# PWR_BUCK_6V_8A.net
KiCad netlist of a schematic drawn in Altium Designer
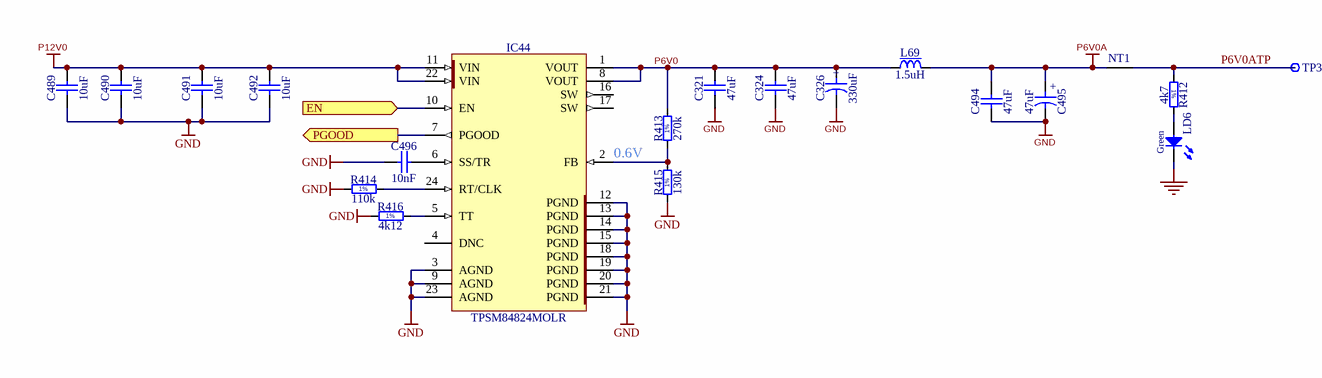
[diagram p0: PWR_BUCK_6V_8A.SchDoc]

(export (version "E")
  (design (tool "Eeschema 10.0.6"))
  (components
    (comp (ref "C321")
      (value "47uF")
      (footprint "CAPC3225X270N")
      (description "Non-polarised capacitor")
      (fields
        (field (name "MANUFACTURER PART NUMBER") "CC1210_47UF_10V_10%_X7R")
        (field (name "MANUFACTURER") "GENERIC")
        (field (name "AUTHOR") "CERN DEM BC")
      )
      (libsource (lib "Capacitors") (part "Capacitor - non polarized"))
    )
    (comp (ref "C324")
      (value "47uF")
      (footprint "CAPC3225X270N")
      (description "Non-polarised capacitor")
      (fields
        (field (name "MANUFACTURER PART NUMBER") "CC1210_47UF_10V_10%_X7R")
        (field (name "MANUFACTURER") "GENERIC")
        (field (name "AUTHOR") "CERN DEM BC")
      )
      (libsource (lib "Capacitors") (part "Capacitor - non polarized"))
    )
    (comp (ref "C326")
      (value "330uF")
      (footprint "CAPMP7343X310N")
      (description "Polarised capacitor")
      (fields
        (field (name "MANUFACTURER PART NUMBER") "T520D337M006ATE015")
        (field (name "MANUFACTURER") "KEMET")
        (field (name "AUTHOR") "CERN DEM JLC")
      )
      (libsource (lib "") (part "Capacitor - polarized_1"))
    )
    (comp (ref "C489")
      (value "10uF")
      (footprint "CAPC2012X95N")
      (description "Non-polarised capacitor")
      (fields
        (field (name "MANUFACTURER PART NUMBER") "CC0805_10UF_25V_10%_X5R")
        (field (name "MANUFACTURER") "GENERIC")
        (field (name "AUTHOR") "CERN DEM JLC")
      )
      (libsource (lib "Capacitors") (part "Capacitor - non polarized"))
    )
    (comp (ref "C490")
      (value "10uF")
      (footprint "CAPC2012X95N")
      (description "Non-polarised capacitor")
      (fields
        (field (name "MANUFACTURER PART NUMBER") "CC0805_10UF_25V_10%_X5R")
        (field (name "MANUFACTURER") "GENERIC")
        (field (name "AUTHOR") "CERN DEM JLC")
      )
      (libsource (lib "Capacitors") (part "Capacitor - non polarized"))
    )
    (comp (ref "C491")
      (value "10uF")
      (footprint "CAPC2012X95N")
      (description "Non-polarised capacitor")
      (fields
        (field (name "MANUFACTURER PART NUMBER") "CC0805_10UF_25V_10%_X5R")
        (field (name "MANUFACTURER") "GENERIC")
        (field (name "AUTHOR") "CERN DEM JLC")
      )
      (libsource (lib "Capacitors") (part "Capacitor - non polarized"))
    )
    (comp (ref "C492")
      (value "10uF")
      (footprint "CAPC2012X95N")
      (description "Non-polarised capacitor")
      (fields
        (field (name "MANUFACTURER PART NUMBER") "CC0805_10UF_25V_10%_X5R")
        (field (name "MANUFACTURER") "GENERIC")
        (field (name "AUTHOR") "CERN DEM JLC")
      )
      (libsource (lib "Capacitors") (part "Capacitor - non polarized"))
    )
    (comp (ref "C494")
      (value "47uF")
      (footprint "CAPC3225X270N")
      (description "Non-polarised capacitor")
      (fields
        (field (name "MANUFACTURER PART NUMBER") "CC1210_47UF_10V_10%_X7R")
        (field (name "MANUFACTURER") "GENERIC")
        (field (name "AUTHOR") "CERN DEM BC")
      )
      (libsource (lib "Capacitors") (part "Capacitor - non polarized"))
    )
    (comp (ref "C495")
      (value "47uF")
      (footprint "CAPMP6032X280N")
      (description "Polarised capacitor")
      (fields
        (field (name "MANUFACTURER PART NUMBER") "CTE6032-28_47UF_16V_10%_LESR0350")
        (field (name "MANUFACTURER") "GENERIC")
        (field (name "AUTHOR") "CERN DEM JLC")
      )
      (libsource (lib "Capacitors") (part "Capacitor - polarized"))
    )
    (comp (ref "C496")
      (value "10nF")
      (footprint "CAPC1005X55N")
      (description "Non-polarised capacitor")
      (fields
        (field (name "PART NUMBER") "CC0402_10NF_16V_10%_X7R")
        (field (name "VOLTAGE") "16V")
        (field (name "AUTHOR") "CERN DEM JLC")
      )
      (libsource (lib "Capacitors") (part "Capacitor - non polarized"))
    )
    (comp (ref "IC44")
      (value "TPSM84824MOLR")
      (footprint "TEXAS_QFM (MOL)")
      (description "4.5V to 17V Input, 0.6V to 10V Output, 8A Power Module")
      (fields (field (name "MANUFACTURER") "TEXAS INSTRUMENTS") (field (name "AUTHOR") "CERN DEM JLC"))
      (libsource (lib "ICs And Semiconductors") (part "TPSM84824"))
    )
    (comp (ref "L69")
      (value "1.5uH")
      (footprint "IND_TDK_SPM6530")
      (description "Inductor With Core")
      (fields
        (field (name "MANUFACTURER PART NUMBER") "SPM6530T-1R5M100")
        (field (name "MANUFACTURER") "TDK")
        (field (name "AUTHOR") "CERN DEM MR")
      )
      (libsource (lib "Inductors & Transformers") (part "Inductor With Magnetic core"))
    )
    (comp (ref "LD6")
      (value "Green")
      (footprint "LED_KINGBRIGHT_KPH-1608CGCK")
      (description "LED Green 1C 2A")
      (fields
        (field (name "PART NUMBER") "LED_KINGBRIGHT_KPH-1608CGCK")
        (field (name "MANUFACTURER") "KINGBRIGHT")
        (field (name "AUTHOR") "CERN DEM JLC")
      )
      (libsource (lib "ICs And Semiconductors") (part "LED Green 1C 2A"))
    )
    (comp (ref "NT1")
      (value "Net Tie")
      (footprint "Net Tie")
      (fields (field (name "AUTHOR") "CERN DEM JLC"))
      (libsource (lib "Eletro-mechanical") (part "Net Tie"))
    )
    (comp (ref "R412")
      (value "4k7")
      (footprint "RESC1005X40N")
      (description "Resistor - 1%")
      (fields
        (field (name "MANUFACTURER PART NUMBER") "R0402_4K7_1%_0.0625W_100PPM")
        (field (name "MANUFACTURER") "GENERIC")
        (field (name "AUTHOR") "CERN DEM JLC")
      )
      (libsource (lib "Resistors") (part "Resistor - 1%"))
    )
    (comp (ref "R413")
      (value "270k")
      (footprint "RESC1005X40N")
      (description "Resistor - 1%")
      (fields
        (field (name "PART NUMBER") "R0402_270K_1%_0.0625W_100PPM")
        (field (name "POWER") "0.0625W")
        (field (name "AUTHOR") "CERN DEM JLC")
      )
      (libsource (lib "Resistors") (part "Resistor - 1%"))
    )
    (comp (ref "R414")
      (value "110k")
      (footprint "RESC1005X40N")
      (description "Resistor - 1%")
      (fields
        (field (name "PART NUMBER") "R0402_110K_1%_0.0625W_100PPM")
        (field (name "POWER") "0.0625W")
        (field (name "AUTHOR") "CERN DEM JLC")
      )
      (libsource (lib "Resistors") (part "Resistor - 1%"))
    )
    (comp (ref "R415")
      (value "130k")
      (footprint "RESC1005X40N")
      (description "Resistor - 1%")
      (fields
        (field (name "PART NUMBER") "R0402_130K_1%_0.0625W_100PPM")
        (field (name "POWER") "0.0625W")
        (field (name "AUTHOR") "CERN DEM JLC")
      )
      (libsource (lib "Resistors") (part "Resistor - 1%"))
    )
    (comp (ref "R416")
      (value "4k12")
      (footprint "RESC1005X40N")
      (description "Resistor - 1%")
      (fields
        (field (name "PART NUMBER") "R0402_4K12_1%_0.0625W_100PPM")
        (field (name "POWER") "0.0625W")
        (field (name "AUTHOR") "CERN DEM JLC")
      )
      (libsource (lib "Resistors") (part "Resistor - 1%"))
    )
    (comp (ref "TP35")
      (value "Test Point")
      (footprint "TPS127")
      (fields (field (name "PART NUMBER") "SMD_PAD_1.27X1.27MM") (field (name "AUTHOR") "CERN DEM JLC"))
      (libsource (lib "Eletro-mechanical") (part "Test Point"))
    )
  )
  (nets
    (net (code "1") (name "/EN") (class "Default")
      (node (ref "IC44") (pin "10") (pinfunction "EN_10") (pintype "input"))
    )
    (net (code "2") (name "/P6V0") (class "Default")
      (node (ref "C321") (pin "2") (pinfunction "2_2") (pintype "passive"))
      (node (ref "C324") (pin "2") (pinfunction "2_2") (pintype "passive"))
      (node (ref "C326") (pin "1") (pinfunction "1_1") (pintype "passive"))
      (node (ref "IC44") (pin "1") (pinfunction "VOUT_1") (pintype "power_in"))
      (node (ref "IC44") (pin "8") (pinfunction "VOUT_8") (pintype "power_in"))
      (node (ref "L69") (pin "1") (pinfunction "1_1") (pintype "passive"))
      (node (ref "R413") (pin "2") (pinfunction "2_2") (pintype "passive"))
    )
    (net (code "3") (name "/P6V0ATP") (class "Default")
      (node (ref "NT1") (pin "2") (pinfunction "2_2") (pintype "bidirectional"))
      (node (ref "R412") (pin "1") (pinfunction "1_1") (pintype "passive"))
      (node (ref "TP35") (pin "1") (pinfunction "1_1") (pintype "bidirectional"))
    )
    (net (code "4") (name "/PGOOD") (class "Default")
      (node (ref "IC44") (pin "7") (pinfunction "PGOOD_7") (pintype "output"))
    )
    (net (code "5") (name "GND") (class "Default")
      (node (ref "C321") (pin "1") (pinfunction "1_1") (pintype "passive"))
      (node (ref "C324") (pin "1") (pinfunction "1_1") (pintype "passive"))
      (node (ref "C326") (pin "2") (pinfunction "2_2") (pintype "passive"))
      (node (ref "C489") (pin "1") (pinfunction "1_1") (pintype "passive"))
      (node (ref "C490") (pin "1") (pinfunction "1_1") (pintype "passive"))
      (node (ref "C491") (pin "1") (pinfunction "1_1") (pintype "passive"))
      (node (ref "C492") (pin "1") (pinfunction "1_1") (pintype "passive"))
      (node (ref "C494") (pin "1") (pinfunction "1_1") (pintype "passive"))
      (node (ref "C495") (pin "2") (pinfunction "2_2") (pintype "passive"))
      (node (ref "C496") (pin "1") (pinfunction "1_1") (pintype "passive"))
      (node (ref "IC44") (pin "12") (pinfunction "PGND_12") (pintype "power_in"))
      (node (ref "IC44") (pin "13") (pinfunction "PGND_13") (pintype "power_in"))
      (node (ref "IC44") (pin "14") (pinfunction "PGND_14") (pintype "power_in"))
      (node (ref "IC44") (pin "15") (pinfunction "PGND_15") (pintype "power_in"))
      (node (ref "IC44") (pin "18") (pinfunction "PGND_18") (pintype "power_in"))
      (node (ref "IC44") (pin "19") (pinfunction "PGND_19") (pintype "power_in"))
      (node (ref "IC44") (pin "20") (pinfunction "PGND_20") (pintype "power_in"))
      (node (ref "IC44") (pin "21") (pinfunction "PGND_21") (pintype "power_in"))
      (node (ref "IC44") (pin "23") (pinfunction "AGND_23") (pintype "power_in"))
      (node (ref "IC44") (pin "3") (pinfunction "AGND_3") (pintype "power_in"))
      (node (ref "IC44") (pin "9") (pinfunction "AGND_9") (pintype "power_in"))
      (node (ref "LD6") (pin "1") (pinfunction "C_1") (pintype "passive"))
      (node (ref "R414") (pin "1") (pinfunction "1_1") (pintype "passive"))
      (node (ref "R415") (pin "1") (pinfunction "1_1") (pintype "passive"))
      (node (ref "R416") (pin "1") (pinfunction "1_1") (pintype "passive"))
    )
    (net (code "6") (name "Net-(IC44-FB)") (class "Default")
      (node (ref "IC44") (pin "2") (pinfunction "FB_2") (pintype "input"))
      (node (ref "R413") (pin "1") (pinfunction "1_1") (pintype "passive"))
      (node (ref "R415") (pin "2") (pinfunction "2_2") (pintype "passive"))
    )
    (net (code "7") (name "Net-(IC44-RT{slash}CLK)") (class "Default")
      (node (ref "IC44") (pin "24") (pinfunction "RT/CLK_24") (pintype "input"))
      (node (ref "R414") (pin "2") (pinfunction "2_2") (pintype "passive"))
    )
    (net (code "8") (name "Net-(IC44-SS{slash}TR)") (class "Default")
      (node (ref "C496") (pin "2") (pinfunction "2_2") (pintype "passive"))
      (node (ref "IC44") (pin "6") (pinfunction "SS/TR_6") (pintype "input"))
    )
    (net (code "9") (name "Net-(IC44-TT)") (class "Default")
      (node (ref "IC44") (pin "5") (pinfunction "TT_5") (pintype "input"))
      (node (ref "R416") (pin "2") (pinfunction "2_2") (pintype "passive"))
    )
    (net (code "10") (name "Net-(LD6-A)") (class "Default")
      (node (ref "LD6") (pin "2") (pinfunction "A_2") (pintype "passive"))
      (node (ref "R412") (pin "2") (pinfunction "2_2") (pintype "passive"))
    )
    (net (code "11") (name "P6V0A") (class "Default")
      (node (ref "C494") (pin "2") (pinfunction "2_2") (pintype "passive"))
      (node (ref "C495") (pin "1") (pinfunction "1_1") (pintype "passive"))
      (node (ref "L69") (pin "2") (pinfunction "2_2") (pintype "passive"))
      (node (ref "NT1") (pin "1") (pinfunction "1_1") (pintype "bidirectional"))
    )
    (net (code "12") (name "P12V0") (class "Default")
      (node (ref "C489") (pin "2") (pinfunction "2_2") (pintype "passive"))
      (node (ref "C490") (pin "2") (pinfunction "2_2") (pintype "passive"))
      (node (ref "C491") (pin "2") (pinfunction "2_2") (pintype "passive"))
      (node (ref "C492") (pin "2") (pinfunction "2_2") (pintype "passive"))
      (node (ref "IC44") (pin "11") (pinfunction "VIN_11") (pintype "input"))
      (node (ref "IC44") (pin "22") (pinfunction "VIN_22") (pintype "input"))
    )
    (net (code "13") (name "unconnected-(IC44-DNC-Pad4)") (class "Default")
      (node (ref "IC44") (pin "4") (pinfunction "DNC_4") (pintype "passive"))
    )
    (net (code "14") (name "unconnected-(IC44-SW-Pad16)") (class "Default")
      (node (ref "IC44") (pin "16") (pinfunction "SW_16") (pintype "output"))
    )
    (net (code "15") (name "unconnected-(IC44-SW-Pad17)") (class "Default")
      (node (ref "IC44") (pin "17") (pinfunction "SW_17") (pintype "output"))
    )
  )
)
